# 328_TQFP_V3.net
KiCad netlist of a schematic drawn in EAGLE
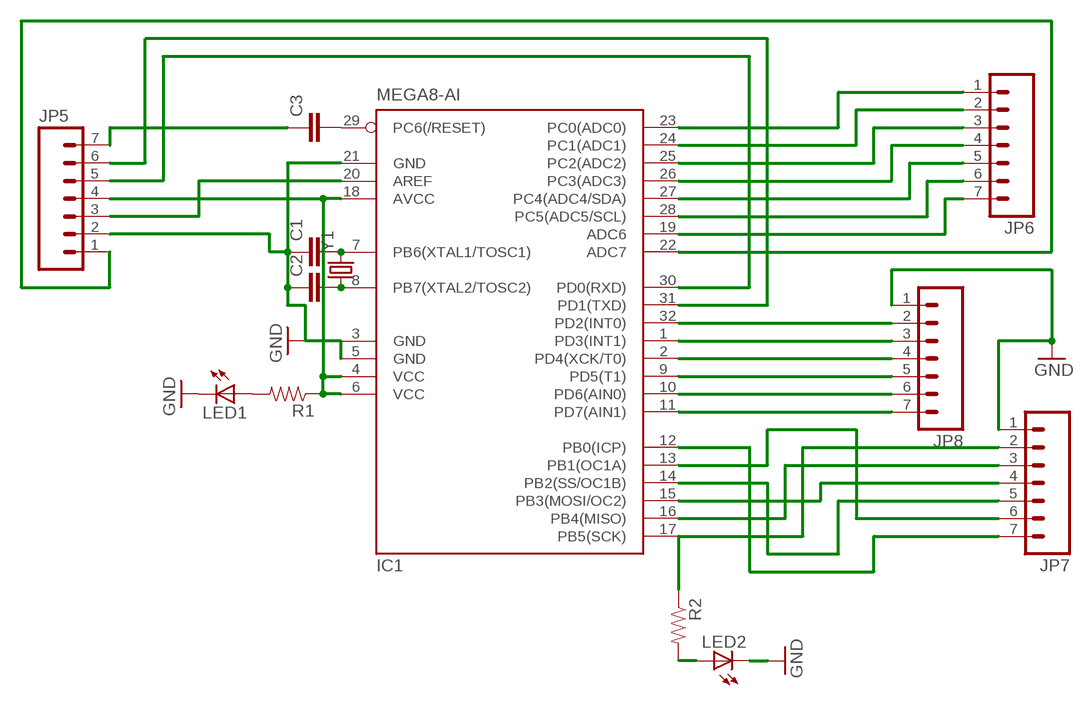
[diagram p0: schematic, sheet 1]

(export (version "E")
  (design (tool "Eeschema 10.0.6"))
  (components
    (comp (ref "C1")
      (value "CAP0603-CAP")
      (footprint "eagle-import:0603-CAP")
      (libsource (lib "eagle-import") (part "CAP0603-CAP"))
    )
    (comp (ref "C2")
      (value "CAP0603-CAP")
      (footprint "eagle-import:0603-CAP")
      (libsource (lib "eagle-import") (part "CAP0603-CAP"))
    )
    (comp (ref "C3")
      (value "CAP0603-CAP")
      (footprint "eagle-import:0603-CAP")
      (libsource (lib "eagle-import") (part "CAP0603-CAP"))
    )
    (comp (ref "IC1")
      (value "MEGA8-AI")
      (footprint "eagle-import:TQFP32-08")
      (fields (field (name "MPN") "ATMEGA8-16AU"))
      (libsource (lib "eagle-import") (part "MEGA8-AI"))
    )
    (comp (ref "JP5")
      (value "M07")
      (footprint "eagle-import:1X07")
      (libsource (lib "eagle-import") (part "M07"))
    )
    (comp (ref "JP6")
      (value "M07")
      (footprint "eagle-import:1X07")
      (libsource (lib "eagle-import") (part "M07"))
    )
    (comp (ref "JP7")
      (value "M07")
      (footprint "eagle-import:1X07")
      (libsource (lib "eagle-import") (part "M07"))
    )
    (comp (ref "JP8")
      (value "M07")
      (footprint "eagle-import:1X07")
      (libsource (lib "eagle-import") (part "M07"))
    )
    (comp (ref "LED1")
      (value "LED0603")
      (footprint "eagle-import:LED-0603")
      (libsource (lib "eagle-import") (part "LED0603"))
    )
    (comp (ref "LED2")
      (value "LED0603")
      (footprint "eagle-import:LED-0603")
      (libsource (lib "eagle-import") (part "LED0603"))
    )
    (comp (ref "R1")
      (value "RESISTOR0603-RES")
      (footprint "eagle-import:0603-RES")
      (libsource (lib "eagle-import") (part "RESISTOR0603-RES"))
    )
    (comp (ref "R2")
      (value "RESISTOR0603-RES")
      (footprint "eagle-import:0603-RES")
      (libsource (lib "eagle-import") (part "RESISTOR0603-RES"))
    )
    (comp (ref "Y1")
      (value "CRYSTAL5X3")
      (footprint "eagle-import:CRYSTAL-SMD-5X3")
      (libsource (lib "eagle-import") (part "CRYSTAL5X3"))
    )
  )
  (nets
    (net (code "1") (name "GND") (class "Default")
      (node (ref "C1") (pin "1") (pinfunction "1_1") (pintype "passive"))
      (node (ref "C2") (pin "1") (pinfunction "1_1") (pintype "passive"))
      (node (ref "IC1") (pin "21") (pinfunction "GND_21") (pintype "power_in"))
      (node (ref "IC1") (pin "3") (pinfunction "GND_3") (pintype "power_in"))
      (node (ref "IC1") (pin "5") (pinfunction "GND_5") (pintype "power_in"))
      (node (ref "JP5") (pin "2") (pinfunction "2_2") (pintype "passive"))
      (node (ref "JP7") (pin "1") (pinfunction "1_1") (pintype "passive"))
      (node (ref "JP8") (pin "1") (pinfunction "1_1") (pintype "passive"))
      (node (ref "LED1") (pin "C") (pinfunction "C_C") (pintype "passive"))
      (node (ref "LED2") (pin "C") (pinfunction "C_C") (pintype "passive"))
    )
    (net (code "2") (name "Net-(C3-Pad1)") (class "Default")
      (node (ref "C3") (pin "1") (pinfunction "1_1") (pintype "passive"))
      (node (ref "JP5") (pin "7") (pinfunction "7_7") (pintype "passive"))
    )
    (net (code "3") (name "Net-(IC1-ADC6)") (class "Default")
      (node (ref "IC1") (pin "19") (pinfunction "ADC6_19") (pintype "bidirectional"))
      (node (ref "JP6") (pin "7") (pinfunction "7_7") (pintype "passive"))
    )
    (net (code "4") (name "Net-(IC1-ADC7)") (class "Default")
      (node (ref "IC1") (pin "22") (pinfunction "ADC7_22") (pintype "bidirectional"))
      (node (ref "JP5") (pin "1") (pinfunction "1_1") (pintype "passive"))
    )
    (net (code "5") (name "Net-(IC1-AREF)") (class "Default")
      (node (ref "IC1") (pin "20") (pinfunction "AREF_20") (pintype "passive"))
      (node (ref "JP5") (pin "3") (pinfunction "3_3") (pintype "passive"))
    )
    (net (code "6") (name "Net-(IC1-AVCC)") (class "Default")
      (node (ref "IC1") (pin "18") (pinfunction "AVCC_18") (pintype "power_in"))
      (node (ref "IC1") (pin "4") (pinfunction "VCC_4") (pintype "power_in"))
      (node (ref "IC1") (pin "6") (pinfunction "VCC_6") (pintype "power_in"))
      (node (ref "JP5") (pin "4") (pinfunction "4_4") (pintype "passive"))
      (node (ref "R1") (pin "1") (pinfunction "1_1") (pintype "passive"))
    )
    (net (code "7") (name "Net-(IC1-PB0(ICP))") (class "Default")
      (node (ref "IC1") (pin "12") (pinfunction "PB0(ICP)_12") (pintype "bidirectional"))
      (node (ref "JP7") (pin "7") (pinfunction "7_7") (pintype "passive"))
    )
    (net (code "8") (name "Net-(IC1-PB1(OC1A))") (class "Default")
      (node (ref "IC1") (pin "13") (pinfunction "PB1(OC1A)_13") (pintype "bidirectional"))
      (node (ref "JP7") (pin "6") (pinfunction "6_6") (pintype "passive"))
    )
    (net (code "9") (name "Net-(IC1-PB2(SS{slash}OC1B))") (class "Default")
      (node (ref "IC1") (pin "14") (pinfunction "PB2(SS/OC1B)_14") (pintype "bidirectional"))
      (node (ref "JP7") (pin "5") (pinfunction "5_5") (pintype "passive"))
    )
    (net (code "10") (name "Net-(IC1-PB3(MOSI{slash}OC2))") (class "Default")
      (node (ref "IC1") (pin "15") (pinfunction "PB3(MOSI/OC2)_15") (pintype "bidirectional"))
      (node (ref "JP7") (pin "4") (pinfunction "4_4") (pintype "passive"))
    )
    (net (code "11") (name "Net-(IC1-PB4(MISO))") (class "Default")
      (node (ref "IC1") (pin "16") (pinfunction "PB4(MISO)_16") (pintype "bidirectional"))
      (node (ref "JP7") (pin "3") (pinfunction "3_3") (pintype "passive"))
    )
    (net (code "12") (name "Net-(IC1-PB5(SCK))") (class "Default")
      (node (ref "IC1") (pin "17") (pinfunction "PB5(SCK)_17") (pintype "bidirectional"))
      (node (ref "JP7") (pin "2") (pinfunction "2_2") (pintype "passive"))
      (node (ref "R2") (pin "1") (pinfunction "1_1") (pintype "passive"))
    )
    (net (code "13") (name "Net-(IC1-PB6(XTAL1{slash}TOSC1))") (class "Default")
      (node (ref "C1") (pin "2") (pinfunction "2_2") (pintype "passive"))
      (node (ref "IC1") (pin "7") (pinfunction "PB6(XTAL1/TOSC1)_7") (pintype "bidirectional"))
      (node (ref "Y1") (pin "3") (pinfunction "2_3") (pintype "passive"))
    )
    (net (code "14") (name "Net-(IC1-PB7(XTAL2{slash}TOSC2))") (class "Default")
      (node (ref "C2") (pin "2") (pinfunction "2_2") (pintype "passive"))
      (node (ref "IC1") (pin "8") (pinfunction "PB7(XTAL2/TOSC2)_8") (pintype "bidirectional"))
      (node (ref "Y1") (pin "1") (pinfunction "1_1") (pintype "passive"))
    )
    (net (code "15") (name "Net-(IC1-PC0(ADC0))") (class "Default")
      (node (ref "IC1") (pin "23") (pinfunction "PC0(ADC0)_23") (pintype "bidirectional"))
      (node (ref "JP6") (pin "1") (pinfunction "1_1") (pintype "passive"))
    )
    (net (code "16") (name "Net-(IC1-PC1(ADC1))") (class "Default")
      (node (ref "IC1") (pin "24") (pinfunction "PC1(ADC1)_24") (pintype "bidirectional"))
      (node (ref "JP6") (pin "2") (pinfunction "2_2") (pintype "passive"))
    )
    (net (code "17") (name "Net-(IC1-PC2(ADC2))") (class "Default")
      (node (ref "IC1") (pin "25") (pinfunction "PC2(ADC2)_25") (pintype "bidirectional"))
      (node (ref "JP6") (pin "3") (pinfunction "3_3") (pintype "passive"))
    )
    (net (code "18") (name "Net-(IC1-PC3(ADC3))") (class "Default")
      (node (ref "IC1") (pin "26") (pinfunction "PC3(ADC3)_26") (pintype "bidirectional"))
      (node (ref "JP6") (pin "4") (pinfunction "4_4") (pintype "passive"))
    )
    (net (code "19") (name "Net-(IC1-PC4(ADC4{slash}SDA))") (class "Default")
      (node (ref "IC1") (pin "27") (pinfunction "PC4(ADC4/SDA)_27") (pintype "bidirectional"))
      (node (ref "JP6") (pin "5") (pinfunction "5_5") (pintype "passive"))
    )
    (net (code "20") (name "Net-(IC1-PC5(ADC5{slash}SCL))") (class "Default")
      (node (ref "IC1") (pin "28") (pinfunction "PC5(ADC5/SCL)_28") (pintype "bidirectional"))
      (node (ref "JP6") (pin "6") (pinfunction "6_6") (pintype "passive"))
    )
    (net (code "21") (name "Net-(IC1-PC6({slash}RESET))") (class "Default")
      (node (ref "C3") (pin "2") (pinfunction "2_2") (pintype "passive"))
      (node (ref "IC1") (pin "29") (pinfunction "PC6(/RESET)_29") (pintype "bidirectional"))
    )
    (net (code "22") (name "Net-(IC1-PD0(RXD))") (class "Default")
      (node (ref "IC1") (pin "30") (pinfunction "PD0(RXD)_30") (pintype "bidirectional"))
      (node (ref "JP5") (pin "5") (pinfunction "5_5") (pintype "passive"))
    )
    (net (code "23") (name "Net-(IC1-PD1(TXD))") (class "Default")
      (node (ref "IC1") (pin "31") (pinfunction "PD1(TXD)_31") (pintype "bidirectional"))
      (node (ref "JP5") (pin "6") (pinfunction "6_6") (pintype "passive"))
    )
    (net (code "24") (name "Net-(IC1-PD2(INT0))") (class "Default")
      (node (ref "IC1") (pin "32") (pinfunction "PD2(INT0)_32") (pintype "bidirectional"))
      (node (ref "JP8") (pin "2") (pinfunction "2_2") (pintype "passive"))
    )
    (net (code "25") (name "Net-(IC1-PD3(INT1))") (class "Default")
      (node (ref "IC1") (pin "1") (pinfunction "PD3(INT1)_1") (pintype "bidirectional"))
      (node (ref "JP8") (pin "3") (pinfunction "3_3") (pintype "passive"))
    )
    (net (code "26") (name "Net-(IC1-PD4(XCK{slash}T0))") (class "Default")
      (node (ref "IC1") (pin "2") (pinfunction "PD4(XCK/T0)_2") (pintype "bidirectional"))
      (node (ref "JP8") (pin "4") (pinfunction "4_4") (pintype "passive"))
    )
    (net (code "27") (name "Net-(IC1-PD5(T1))") (class "Default")
      (node (ref "IC1") (pin "9") (pinfunction "PD5(T1)_9") (pintype "bidirectional"))
      (node (ref "JP8") (pin "5") (pinfunction "5_5") (pintype "passive"))
    )
    (net (code "28") (name "Net-(IC1-PD6(AIN0))") (class "Default")
      (node (ref "IC1") (pin "10") (pinfunction "PD6(AIN0)_10") (pintype "bidirectional"))
      (node (ref "JP8") (pin "6") (pinfunction "6_6") (pintype "passive"))
    )
    (net (code "29") (name "Net-(IC1-PD7(AIN1))") (class "Default")
      (node (ref "IC1") (pin "11") (pinfunction "PD7(AIN1)_11") (pintype "bidirectional"))
      (node (ref "JP8") (pin "7") (pinfunction "7_7") (pintype "passive"))
    )
    (net (code "30") (name "Net-(LED1-PadA)") (class "Default")
      (node (ref "LED1") (pin "A") (pinfunction "A_A") (pintype "passive"))
      (node (ref "R1") (pin "2") (pinfunction "2_2") (pintype "passive"))
    )
    (net (code "31") (name "Net-(LED2-PadA)") (class "Default")
      (node (ref "LED2") (pin "A") (pinfunction "A_A") (pintype "passive"))
      (node (ref "R2") (pin "2") (pinfunction "2_2") (pintype "passive"))
    )
  )
)
